# tracker_v3.net
KiCad netlist of a schematic drawn in EAGLE
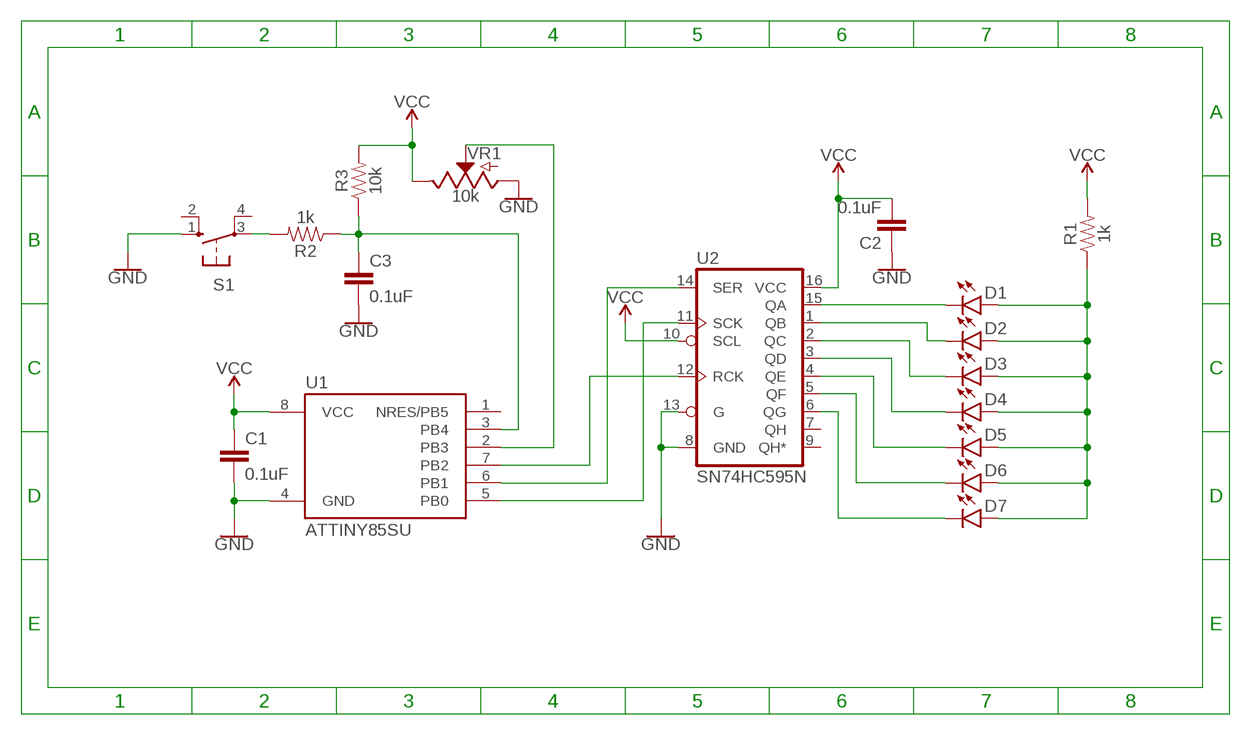
[diagram p0: schematic, sheet 1]

(export (version "E")
  (design (tool "Eeschema 10.0.6"))
  (components
    (comp (ref "C1")
      (value "0.1uF")
      (footprint "eagle-import:0603")
      (libsource (lib "eagle-import") (part "0.1UF-0603-25V-(+80/-20%)"))
    )
    (comp (ref "C2")
      (value "0.1uF")
      (footprint "eagle-import:0603")
      (libsource (lib "eagle-import") (part "0.1UF-0603-25V-(+80/-20%)"))
    )
    (comp (ref "C3")
      (value "0.1uF")
      (footprint "eagle-import:0603")
      (libsource (lib "eagle-import") (part "0.1UF-0603-25V-(+80/-20%)"))
    )
    (comp (ref "D1")
      (value "LED3MM")
      (footprint "eagle-import:LED_3MM")
      (libsource (lib "eagle-import") (part "LED3MM"))
    )
    (comp (ref "D2")
      (value "LED3MM")
      (footprint "eagle-import:LED_3MM")
      (libsource (lib "eagle-import") (part "LED3MM"))
    )
    (comp (ref "D3")
      (value "LED3MM")
      (footprint "eagle-import:LED_3MM")
      (libsource (lib "eagle-import") (part "LED3MM"))
    )
    (comp (ref "D4")
      (value "LED3MM")
      (footprint "eagle-import:LED_3MM")
      (libsource (lib "eagle-import") (part "LED3MM"))
    )
    (comp (ref "D5")
      (value "LED3MM")
      (footprint "eagle-import:LED_3MM")
      (libsource (lib "eagle-import") (part "LED3MM"))
    )
    (comp (ref "D6")
      (value "LED3MM")
      (footprint "eagle-import:LED_3MM")
      (libsource (lib "eagle-import") (part "LED3MM"))
    )
    (comp (ref "D7")
      (value "LED3MM")
      (footprint "eagle-import:LED_3MM")
      (libsource (lib "eagle-import") (part "LED3MM"))
    )
    (comp (ref "R1")
      (value "1k")
      (footprint "eagle-import:AXIAL-0.3")
      (libsource (lib "eagle-import") (part "1KOHM-HORIZ-1/4W-1%"))
    )
    (comp (ref "R2")
      (value "1k")
      (footprint "eagle-import:AXIAL-0.3")
      (libsource (lib "eagle-import") (part "1KOHM-HORIZ-1/4W-1%"))
    )
    (comp (ref "R3")
      (value "10k")
      (footprint "eagle-import:AXIAL-0.3")
      (libsource (lib "eagle-import") (part "10KOHM-HORIZ-1/4W-1%"))
    )
    (comp (ref "S1")
      (value "10-XX")
      (footprint "eagle-import:B3F-10XX")
      (fields (field (name "MPN") "B3F-1000"))
      (libsource (lib "eagle-import") (part "10-XX"))
    )
    (comp (ref "U1")
      (value "ATTINY85SU")
      (footprint "eagle-import:ATTINY85")
      (libsource (lib "eagle-import") (part "ATTINY85SU"))
    )
    (comp (ref "U2")
      (value "SN74HC595N")
      (footprint "eagle-import:DIP16")
      (libsource (lib "eagle-import") (part "74595NHC"))
    )
    (comp (ref "VR1")
      (value "10k")
      (footprint "eagle-import:POT-PTH-ALPS-KIT")
      (libsource (lib "eagle-import") (part "POTENTIOMETER-PTH-9MM-1/20W-20%-KIT"))
    )
  )
  (nets
    (net (code "1") (name "GND") (class "Default")
      (node (ref "C1") (pin "2") (pinfunction "2_2") (pintype "passive"))
      (node (ref "C2") (pin "1") (pinfunction "1_1") (pintype "passive"))
      (node (ref "C3") (pin "2") (pinfunction "2_2") (pintype "passive"))
      (node (ref "S1") (pin "1") (pinfunction "S_1") (pintype "passive"))
      (node (ref "U1") (pin "4") (pinfunction "GND_4") (pintype "power_in"))
      (node (ref "U2") (pin "13") (pinfunction "G_13") (pintype "input"))
      (node (ref "U2") (pin "8") (pinfunction "GND_8") (pintype "power_in"))
      (node (ref "VR1") (pin "P$3") (pinfunction "A_P$3") (pintype "passive"))
    )
    (net (code "2") (name "Net-(D1-C)") (class "Default")
      (node (ref "D1") (pin "K") (pinfunction "C_K") (pintype "passive"))
      (node (ref "U2") (pin "15") (pinfunction "QA_15") (pintype "tri_state"))
    )
    (net (code "3") (name "Net-(D2-C)") (class "Default")
      (node (ref "D2") (pin "K") (pinfunction "C_K") (pintype "passive"))
      (node (ref "U2") (pin "1") (pinfunction "QB_1") (pintype "tri_state"))
    )
    (net (code "4") (name "Net-(D3-C)") (class "Default")
      (node (ref "D3") (pin "K") (pinfunction "C_K") (pintype "passive"))
      (node (ref "U2") (pin "2") (pinfunction "QC_2") (pintype "tri_state"))
    )
    (net (code "5") (name "Net-(D4-C)") (class "Default")
      (node (ref "D4") (pin "K") (pinfunction "C_K") (pintype "passive"))
      (node (ref "U2") (pin "3") (pinfunction "QD_3") (pintype "tri_state"))
    )
    (net (code "6") (name "Net-(D5-C)") (class "Default")
      (node (ref "D5") (pin "K") (pinfunction "C_K") (pintype "passive"))
      (node (ref "U2") (pin "4") (pinfunction "QE_4") (pintype "tri_state"))
    )
    (net (code "7") (name "Net-(D6-C)") (class "Default")
      (node (ref "D6") (pin "K") (pinfunction "C_K") (pintype "passive"))
      (node (ref "U2") (pin "5") (pinfunction "QF_5") (pintype "tri_state"))
    )
    (net (code "8") (name "Net-(D7-C)") (class "Default")
      (node (ref "D7") (pin "K") (pinfunction "C_K") (pintype "passive"))
      (node (ref "U2") (pin "6") (pinfunction "QG_6") (pintype "tri_state"))
    )
    (net (code "9") (name "Net-(R1-1)") (class "Default")
      (node (ref "D1") (pin "A") (pinfunction "A_A") (pintype "passive"))
      (node (ref "D2") (pin "A") (pinfunction "A_A") (pintype "passive"))
      (node (ref "D3") (pin "A") (pinfunction "A_A") (pintype "passive"))
      (node (ref "D4") (pin "A") (pinfunction "A_A") (pintype "passive"))
      (node (ref "D5") (pin "A") (pinfunction "A_A") (pintype "passive"))
      (node (ref "D6") (pin "A") (pinfunction "A_A") (pintype "passive"))
      (node (ref "D7") (pin "A") (pinfunction "A_A") (pintype "passive"))
      (node (ref "R1") (pin "P$1") (pinfunction "1_P$1") (pintype "passive"))
    )
    (net (code "10") (name "Net-(R2-1)") (class "Default")
      (node (ref "C3") (pin "1") (pinfunction "1_1") (pintype "passive"))
      (node (ref "R2") (pin "P$1") (pinfunction "1_P$1") (pintype "passive"))
      (node (ref "R3") (pin "P$1") (pinfunction "1_P$1") (pintype "passive"))
      (node (ref "U1") (pin "3") (pinfunction "PB4_3") (pintype "bidirectional"))
    )
    (net (code "11") (name "Net-(R2-2)") (class "Default")
      (node (ref "R2") (pin "P$2") (pinfunction "2_P$2") (pintype "passive"))
      (node (ref "S1") (pin "3") (pinfunction "P_3") (pintype "passive"))
    )
    (net (code "12") (name "Net-(U1-PB0)") (class "Default")
      (node (ref "U1") (pin "5") (pinfunction "PB0_5") (pintype "bidirectional"))
      (node (ref "U2") (pin "11") (pinfunction "SCK_11") (pintype "input"))
    )
    (net (code "13") (name "Net-(U1-PB1)") (class "Default")
      (node (ref "U1") (pin "6") (pinfunction "PB1_6") (pintype "bidirectional"))
      (node (ref "U2") (pin "14") (pinfunction "SER_14") (pintype "input"))
    )
    (net (code "14") (name "Net-(U1-PB2)") (class "Default")
      (node (ref "U1") (pin "7") (pinfunction "PB2_7") (pintype "bidirectional"))
      (node (ref "U2") (pin "12") (pinfunction "RCK_12") (pintype "input"))
    )
    (net (code "15") (name "Net-(U1-PB3)") (class "Default")
      (node (ref "U1") (pin "2") (pinfunction "PB3_2") (pintype "bidirectional"))
      (node (ref "VR1") (pin "P$2") (pinfunction "S_P$2") (pintype "passive"))
    )
    (net (code "16") (name "VCC") (class "Default")
      (node (ref "C1") (pin "1") (pinfunction "1_1") (pintype "passive"))
      (node (ref "C2") (pin "2") (pinfunction "2_2") (pintype "passive"))
      (node (ref "R1") (pin "P$2") (pinfunction "2_P$2") (pintype "passive"))
      (node (ref "R3") (pin "P$2") (pinfunction "2_P$2") (pintype "passive"))
      (node (ref "U1") (pin "8") (pinfunction "VCC_8") (pintype "power_in"))
      (node (ref "U2") (pin "10") (pinfunction "SCL_10") (pintype "input"))
      (node (ref "U2") (pin "16") (pinfunction "VCC_16") (pintype "power_in"))
      (node (ref "VR1") (pin "P$1") (pinfunction "E_P$1") (pintype "passive"))
    )
    (net (code "17") (name "unconnected-(S1-P1-Pad4)") (class "Default")
      (node (ref "S1") (pin "4") (pinfunction "P1_4") (pintype "passive"))
    )
    (net (code "18") (name "unconnected-(S1-S1-Pad2)") (class "Default")
      (node (ref "S1") (pin "2") (pinfunction "S1_2") (pintype "passive"))
    )
    (net (code "19") (name "unconnected-(U1-NRES{slash}PB5-Pad1)") (class "Default")
      (node (ref "U1") (pin "1") (pinfunction "NRES/PB5_1") (pintype "bidirectional"))
    )
    (net (code "20") (name "unconnected-(U2-QH*-Pad9)") (class "Default")
      (node (ref "U2") (pin "9") (pinfunction "QH*_9") (pintype "tri_state"))
    )
    (net (code "21") (name "unconnected-(U2-QH-Pad7)") (class "Default")
      (node (ref "U2") (pin "7") (pinfunction "QH_7") (pintype "tri_state"))
    )
  )
)
